# Comm_Interface.net
KiCad netlist of a schematic drawn in Altium Designer
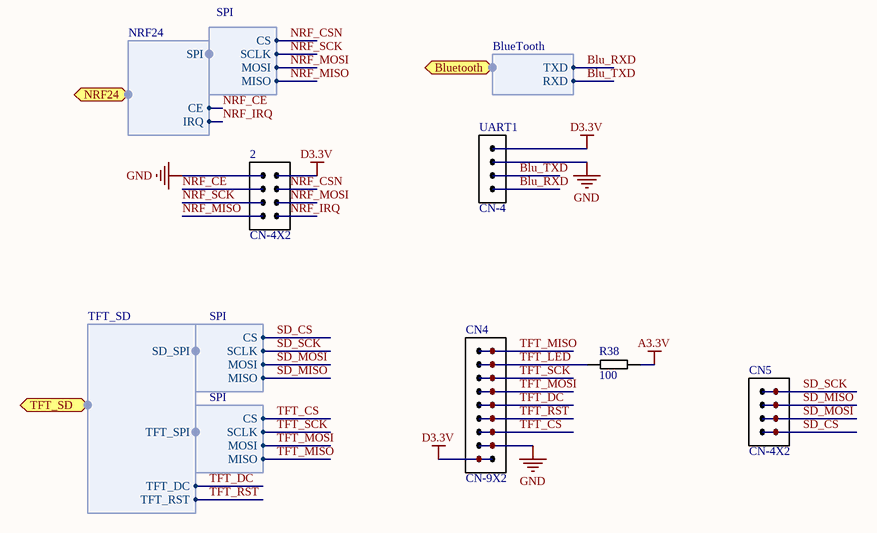
[diagram p0: Comm_Interface.SchDoc]

(export (version "E")
  (design (tool "Eeschema 10.0.6"))
  (components
    (comp (ref "2") (value "CN-4X2") (footprint "IDC-8") (libsource (lib "开关·连接器") (part "CN-4X2")))
    (comp (ref "CN4") (value "CN-9X2") (footprint "IDC-18") (libsource (lib "开关·连接器") (part "CN-9X2")))
    (comp (ref "CN5") (value "CN-4X2") (footprint "IDC-8") (libsource (lib "开关·连接器") (part "CN-4X2")))
    (comp (ref "R38")
      (value "100")
      (footprint "0805-R")
      (description "贴片")
      (libsource (lib "authuir") (part "RES_Chip"))
    )
    (comp (ref "UART1") (value "CN-4") (footprint "SIP-4") (libsource (lib "开关·连接器") (part "CN-4")))
  )
  (nets
    (net (code "4") (name "/Blu_RXD") (class "Default")
      (node (ref "UART1") (pin "4") (pinfunction "4_4") (pintype "passive"))
    )
    (net (code "5") (name "/Blu_TXD") (class "Default")
      (node (ref "UART1") (pin "3") (pinfunction "3_3") (pintype "passive"))
    )
    (net (code "6") (name "/NRF_CE") (class "Default")
      (node (ref "2") (pin "3") (pinfunction "3_3") (pintype "passive"))
    )
    (net (code "7") (name "/NRF_CSN") (class "Default")
      (node (ref "2") (pin "4") (pinfunction "4_4") (pintype "passive"))
    )
    (net (code "8") (name "/NRF_IRQ") (class "Default")
      (node (ref "2") (pin "8") (pinfunction "8_8") (pintype "passive"))
    )
    (net (code "9") (name "/NRF_MISO") (class "Default")
      (node (ref "2") (pin "7") (pinfunction "7_7") (pintype "passive"))
    )
    (net (code "10") (name "/NRF_MOSI") (class "Default")
      (node (ref "2") (pin "6") (pinfunction "6_6") (pintype "passive"))
    )
    (net (code "11") (name "/NRF_SCK") (class "Default")
      (node (ref "2") (pin "5") (pinfunction "5_5") (pintype "passive"))
    )
    (net (code "12") (name "/SD_CS") (class "Default")
      (node (ref "CN5") (pin "7") (pinfunction "7_7") (pintype "passive"))
      (node (ref "CN5") (pin "8") (pinfunction "8_8") (pintype "passive"))
    )
    (net (code "13") (name "/SD_MISO") (class "Default")
      (node (ref "CN5") (pin "3") (pinfunction "3_3") (pintype "passive"))
      (node (ref "CN5") (pin "4") (pinfunction "4_4") (pintype "passive"))
    )
    (net (code "14") (name "/SD_MOSI") (class "Default")
      (node (ref "CN5") (pin "5") (pinfunction "5_5") (pintype "passive"))
      (node (ref "CN5") (pin "6") (pinfunction "6_6") (pintype "passive"))
    )
    (net (code "15") (name "/SD_SCK") (class "Default")
      (node (ref "CN5") (pin "1") (pinfunction "1_1") (pintype "passive"))
      (node (ref "CN5") (pin "2") (pinfunction "2_2") (pintype "passive"))
    )
    (net (code "16") (name "/TFT_CS") (class "Default")
      (node (ref "CN4") (pin "13") (pinfunction "13_13") (pintype "passive"))
      (node (ref "CN4") (pin "14") (pinfunction "14_14") (pintype "passive"))
    )
    (net (code "17") (name "/TFT_DC") (class "Default")
      (node (ref "CN4") (pin "10") (pinfunction "10_10") (pintype "passive"))
      (node (ref "CN4") (pin "9") (pinfunction "9_9") (pintype "passive"))
    )
    (net (code "18") (name "/TFT_LED") (class "Default")
      (node (ref "CN4") (pin "3") (pinfunction "3_3") (pintype "passive"))
      (node (ref "CN4") (pin "4") (pinfunction "4_4") (pintype "passive"))
      (node (ref "R38") (pin "1") (pinfunction "1_1") (pintype "passive"))
    )
    (net (code "19") (name "/TFT_MISO") (class "Default")
      (node (ref "CN4") (pin "1") (pinfunction "1_1") (pintype "passive"))
      (node (ref "CN4") (pin "2") (pinfunction "2_2") (pintype "passive"))
    )
    (net (code "20") (name "/TFT_MOSI") (class "Default")
      (node (ref "CN4") (pin "7") (pinfunction "7_7") (pintype "passive"))
      (node (ref "CN4") (pin "8") (pinfunction "8_8") (pintype "passive"))
    )
    (net (code "21") (name "/TFT_RST") (class "Default")
      (node (ref "CN4") (pin "11") (pinfunction "11_11") (pintype "passive"))
      (node (ref "CN4") (pin "12") (pinfunction "12_12") (pintype "passive"))
    )
    (net (code "22") (name "/TFT_SCK") (class "Default")
      (node (ref "CN4") (pin "5") (pinfunction "5_5") (pintype "passive"))
      (node (ref "CN4") (pin "6") (pinfunction "6_6") (pintype "passive"))
    )
    (net (code "26") (name "A3.3V") (class "Default")
      (node (ref "R38") (pin "2") (pinfunction "2_2") (pintype "passive"))
    )
    (net (code "27") (name "D3.3V") (class "Default")
      (node (ref "2") (pin "2") (pinfunction "2_2") (pintype "passive"))
      (node (ref "CN4") (pin "17") (pinfunction "17_17") (pintype "passive"))
      (node (ref "CN4") (pin "18") (pinfunction "18_18") (pintype "passive"))
      (node (ref "UART1") (pin "1") (pinfunction "1_1") (pintype "passive"))
    )
    (net (code "28") (name "GND") (class "Default")
      (node (ref "2") (pin "1") (pinfunction "1_1") (pintype "passive"))
      (node (ref "CN4") (pin "15") (pinfunction "15_15") (pintype "passive"))
      (node (ref "CN4") (pin "16") (pinfunction "16_16") (pintype "passive"))
      (node (ref "UART1") (pin "2") (pinfunction "2_2") (pintype "passive"))
    )
  )
)
